# Astable_555_timer.net
KiCad netlist of a schematic drawn in EAGLE
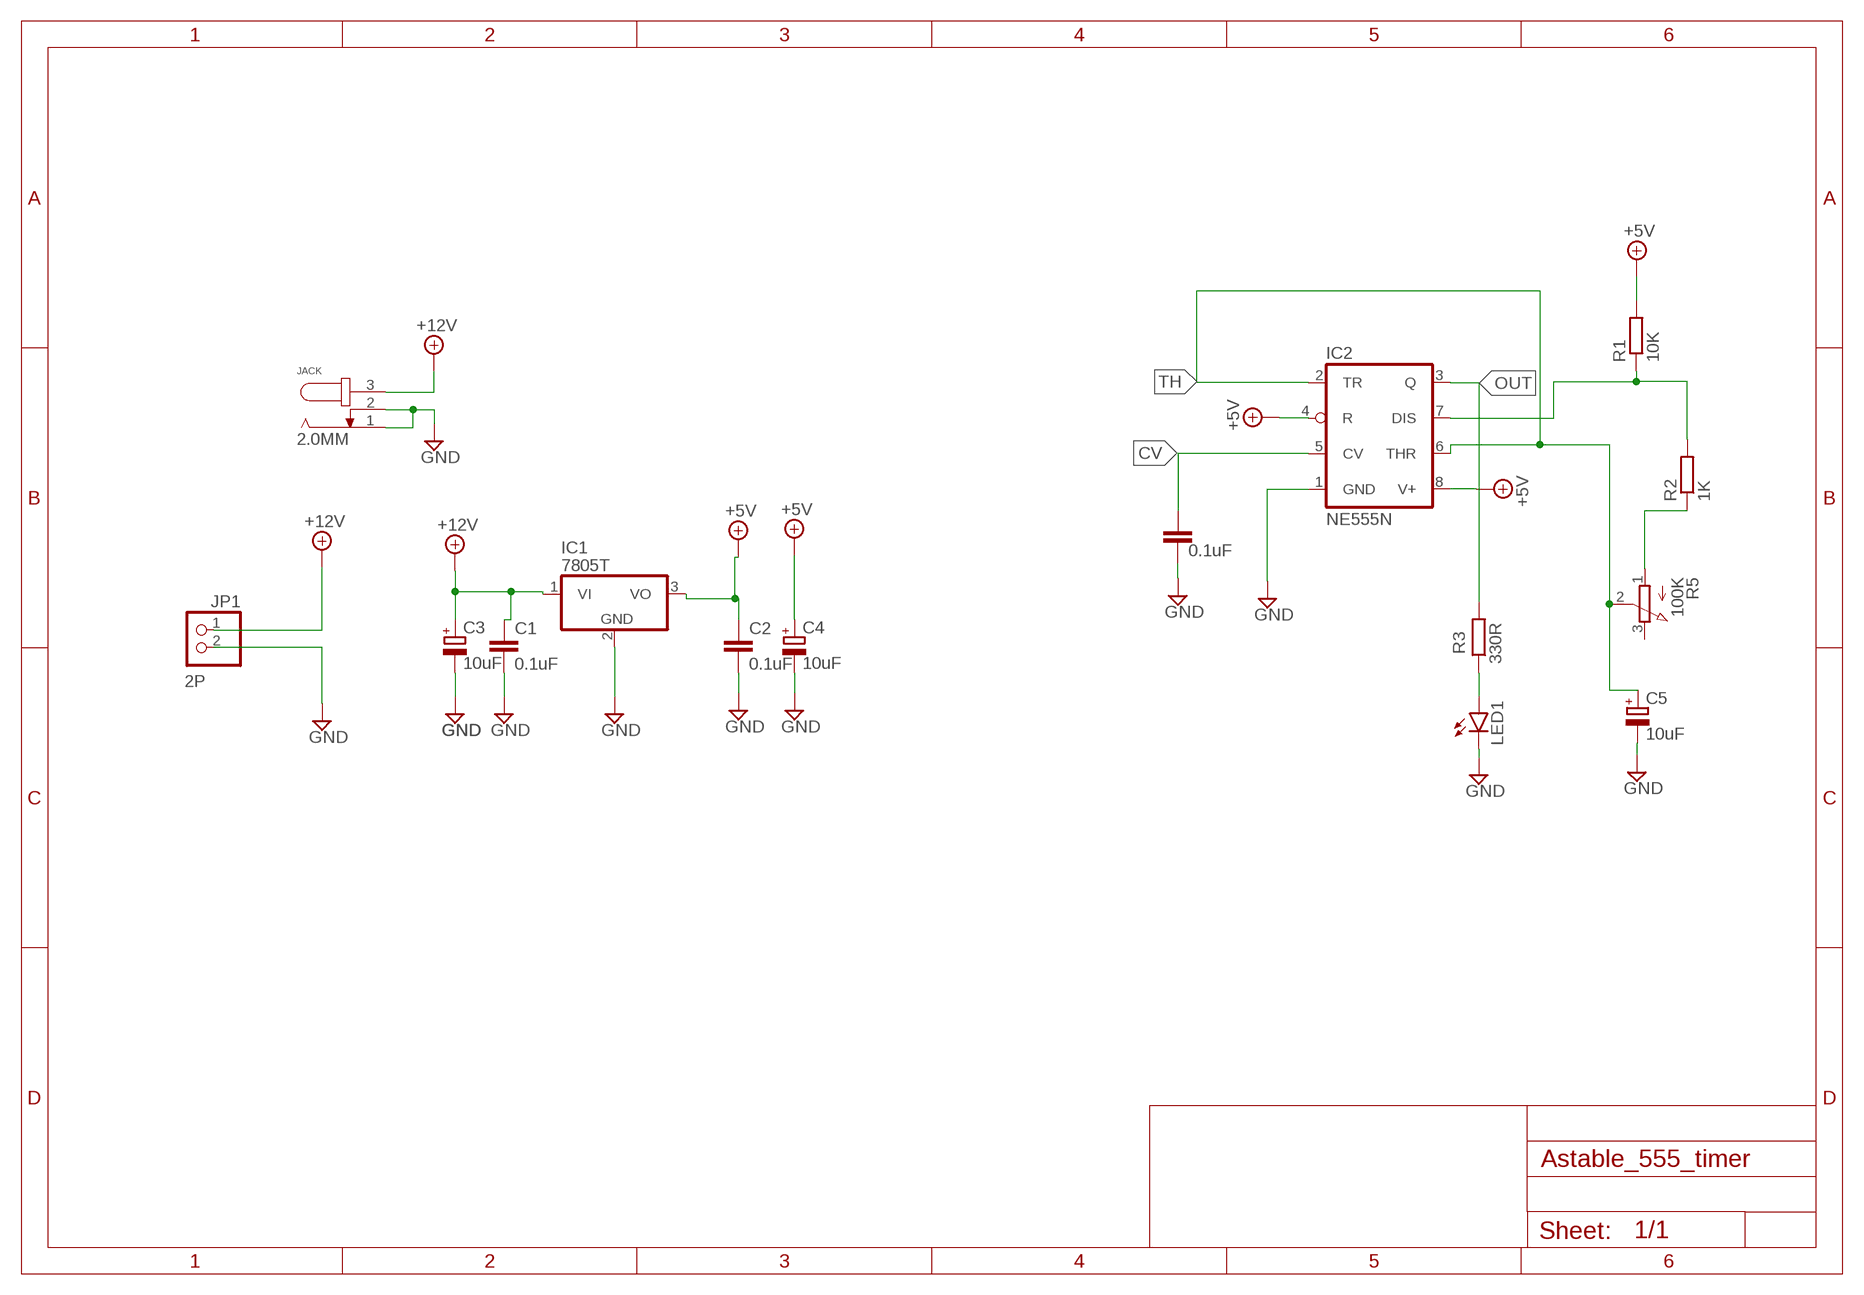
[diagram p0: schematic, sheet 1]

(export (version "E")
  (design (tool "Eeschema 10.0.6"))
  (components
    (comp (ref "C1")
      (value "0.1uF")
      (footprint "eagle-import:C050-030X075")
      (libsource (lib "eagle-import") (part "C-EU050-030X075"))
    )
    (comp (ref "C2")
      (value "0.1uF")
      (footprint "eagle-import:C050-030X075")
      (libsource (lib "eagle-import") (part "C-EU050-030X075"))
    )
    (comp (ref "C3")
      (value "10uF")
      (footprint "eagle-import:E3,5-8")
      (libsource (lib "eagle-import") (part "CPOL-EUE3.5-8"))
    )
    (comp (ref "C4")
      (value "10uF")
      (footprint "eagle-import:E3,5-8")
      (libsource (lib "eagle-import") (part "CPOL-EUE3.5-8"))
    )
    (comp (ref "C5")
      (value "10uF")
      (footprint "eagle-import:E3,5-8")
      (libsource (lib "eagle-import") (part "CPOL-EUE3.5-8"))
    )
    (comp (ref "C6")
      (value "0.1uF")
      (footprint "eagle-import:C050-030X075")
      (libsource (lib "eagle-import") (part "C-EU050-030X075"))
    )
    (comp (ref "IC1")
      (value "7805T")
      (footprint "eagle-import:TO220H")
      (libsource (lib "eagle-import") (part "78T05"))
    )
    (comp (ref "IC2")
      (value "NE555N")
      (footprint "eagle-import:DIL08")
      (libsource (lib "eagle-import") (part "555NNE"))
    )
    (comp (ref "JACK")
      (value "2.0MM")
      (footprint "eagle-import:SPC4078")
      (libsource (lib "eagle-import") (part "JACK-PLUG1"))
    )
    (comp (ref "JP1")
      (value "2P")
      (footprint "eagle-import:1X02")
      (libsource (lib "eagle-import") (part "PINHD-1X2"))
    )
    (comp (ref "LED1")
      (value "LED5MM")
      (footprint "eagle-import:LED5MM")
      (libsource (lib "eagle-import") (part "LED5MM"))
    )
    (comp (ref "R1")
      (value "10K")
      (footprint "eagle-import:0207_10")
      (libsource (lib "eagle-import") (part "R-EU_0207/10"))
    )
    (comp (ref "R2")
      (value "1K")
      (footprint "eagle-import:0207_10")
      (libsource (lib "eagle-import") (part "R-EU_0207/10"))
    )
    (comp (ref "R3")
      (value "330R")
      (footprint "eagle-import:0207_10")
      (libsource (lib "eagle-import") (part "R-EU_0207/10"))
    )
    (comp (ref "R5")
      (value "100K")
      (footprint "eagle-import:3RP_1610N")
      (libsource (lib "eagle-import") (part "3RP/1610N"))
    )
  )
  (nets
    (net (code "1") (name "+5V") (class "Default")
      (node (ref "C2") (pin "1") (pinfunction "1_1") (pintype "passive"))
      (node (ref "C4") (pin "+") (pinfunction "+_+") (pintype "passive"))
      (node (ref "IC1") (pin "3") (pinfunction "VO_3") (pintype "passive"))
      (node (ref "IC2") (pin "4") (pinfunction "R_4") (pintype "input"))
      (node (ref "IC2") (pin "8") (pinfunction "V+_8") (pintype "power_in"))
      (node (ref "R1") (pin "2") (pinfunction "2_2") (pintype "passive"))
    )
    (net (code "2") (name "+12V") (class "Default")
      (node (ref "C1") (pin "1") (pinfunction "1_1") (pintype "passive"))
      (node (ref "C3") (pin "+") (pinfunction "+_+") (pintype "passive"))
      (node (ref "IC1") (pin "1") (pinfunction "VI_1") (pintype "input"))
      (node (ref "JACK") (pin "3") (pinfunction "3_3") (pintype "passive"))
      (node (ref "JP1") (pin "1") (pinfunction "1_1") (pintype "passive"))
    )
    (net (code "3") (name "CV") (class "Default")
      (node (ref "C6") (pin "1") (pinfunction "1_1") (pintype "passive"))
      (node (ref "IC2") (pin "5") (pinfunction "CV_5") (pintype "input"))
    )
    (net (code "4") (name "GND") (class "Default")
      (node (ref "C1") (pin "2") (pinfunction "2_2") (pintype "passive"))
      (node (ref "C2") (pin "2") (pinfunction "2_2") (pintype "passive"))
      (node (ref "C3") (pin "-") (pinfunction "-_-") (pintype "passive"))
      (node (ref "C4") (pin "-") (pinfunction "-_-") (pintype "passive"))
      (node (ref "C5") (pin "-") (pinfunction "-_-") (pintype "passive"))
      (node (ref "C6") (pin "2") (pinfunction "2_2") (pintype "passive"))
      (node (ref "IC1") (pin "2") (pinfunction "GND_2") (pintype "passive"))
      (node (ref "IC2") (pin "1") (pinfunction "GND_1") (pintype "power_in"))
      (node (ref "JACK") (pin "1") (pinfunction "1_1") (pintype "passive"))
      (node (ref "JACK") (pin "2") (pinfunction "2_2") (pintype "passive"))
      (node (ref "JP1") (pin "2") (pinfunction "2_2") (pintype "passive"))
      (node (ref "LED1") (pin "K") (pinfunction "C_K") (pintype "passive"))
    )
    (net (code "5") (name "Net-(IC2-DIS)") (class "Default")
      (node (ref "IC2") (pin "7") (pinfunction "DIS_7") (pintype "input"))
      (node (ref "R1") (pin "1") (pinfunction "1_1") (pintype "passive"))
      (node (ref "R2") (pin "2") (pinfunction "2_2") (pintype "passive"))
    )
    (net (code "6") (name "Net-(LED1-PadA)") (class "Default")
      (node (ref "LED1") (pin "A") (pinfunction "A_A") (pintype "passive"))
      (node (ref "R3") (pin "1") (pinfunction "1_1") (pintype "passive"))
    )
    (net (code "7") (name "Net-(R5-A)") (class "Default")
      (node (ref "R2") (pin "1") (pinfunction "1_1") (pintype "passive"))
      (node (ref "R5") (pin "1") (pinfunction "A_1") (pintype "passive"))
    )
    (net (code "8") (name "OUT") (class "Default")
      (node (ref "IC2") (pin "3") (pinfunction "Q_3") (pintype "output"))
      (node (ref "R3") (pin "2") (pinfunction "2_2") (pintype "passive"))
    )
    (net (code "9") (name "TH") (class "Default")
      (node (ref "C5") (pin "+") (pinfunction "+_+") (pintype "passive"))
      (node (ref "IC2") (pin "2") (pinfunction "TR_2") (pintype "input"))
      (node (ref "IC2") (pin "6") (pinfunction "THR_6") (pintype "input"))
      (node (ref "R5") (pin "2") (pinfunction "S_2") (pintype "passive"))
    )
    (net (code "10") (name "unconnected-(R5-E-Pad3)") (class "Default")
      (node (ref "R5") (pin "3") (pinfunction "E_3") (pintype "passive"))
    )
  )
)
